# Motor_Control_-_Phase_B.net
KiCad netlist of a schematic drawn in Altium Designer
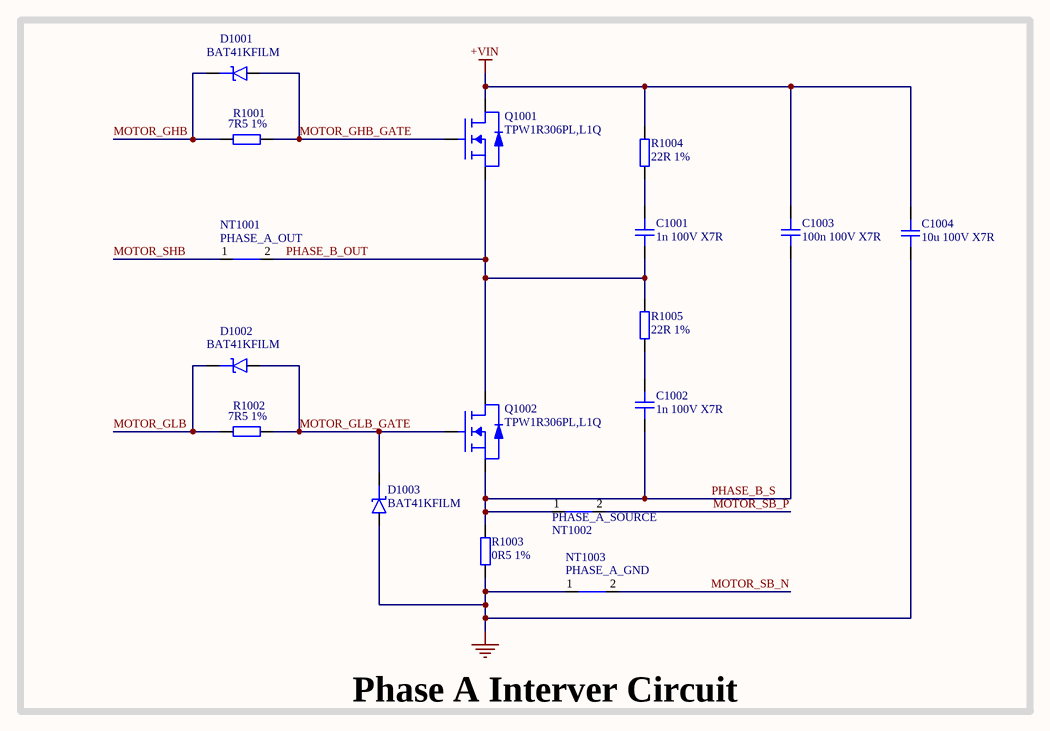
[diagram p0: Motor Control - Phase B.SchDoc]

(export (version "E")
  (design (tool "Eeschema 10.0.6"))
  (components
    (comp (ref "C1001")
      (value "1n 100V X7R")
      (footprint "CAP_0805")
      (description "Capacitor SMD 0805")
      (fields
        (field (name "MANUFACTURER") "Kyocera AVX")
        (field (name "MANUFACTURER PART NUMBER") "08051C102JAT2A")
      )
      (libsource (lib "Schematic-Lib-PhilsLab") (part "CAP_0805"))
    )
    (comp (ref "C1002")
      (value "1n 100V X7R")
      (footprint "CAP_0805")
      (description "Capacitor SMD 0805")
      (fields
        (field (name "MANUFACTURER") "Kyocera AVX")
        (field (name "MANUFACTURER PART NUMBER") "08051C102JAT2A")
      )
      (libsource (lib "Schematic-Lib-PhilsLab") (part "CAP_0805"))
    )
    (comp (ref "C1003")
      (value "100n 100V X7R")
      (footprint "CAP_1206")
      (description "Capacitor SMD 1206")
      (fields
        (field (name "MANUFACTURER") "YAGEO")
        (field (name "MANUFACTURER PART NUMBER") "CC1206JKX7R0BB104")
      )
      (libsource (lib "Schematic-Lib-PhilsLab") (part "CAP_1206"))
    )
    (comp (ref "C1004")
      (value "10u 100V X7R")
      (footprint "CAP_1210")
      (description "Capacitor SMD 1210")
      (fields
        (field (name "MANUFACTURER") "PSA(Prosperity Dielectrics)")
        (field (name "MANUFACTURER PART NUMBER") "FS32X106K101EGG")
      )
      (libsource (lib "Schematic-Lib-PhilsLab") (part "CAP_1210"))
    )
    (comp (ref "D1001")
      (value "BAT41KFILM")
      (footprint "SOD-523")
      (description "Diode Schottky SMD SOD-323")
      (fields (field (name "MANUFACTURER") "STMicroelectronics"))
      (libsource (lib "Schematic-Lib-PhilsLab") (part "D_SCHOTTKY_SOD_523"))
    )
    (comp (ref "D1002")
      (value "BAT41KFILM")
      (footprint "SOD-523")
      (description "Diode Schottky SMD SOD-323")
      (fields (field (name "MANUFACTURER") "STMicroelectronics"))
      (libsource (lib "Schematic-Lib-PhilsLab") (part "D_SCHOTTKY_SOD_523"))
    )
    (comp (ref "D1003")
      (value "BAT41KFILM")
      (footprint "SOD-523")
      (description "Diode Schottky SMD SOD-323")
      (fields (field (name "MANUFACTURER") "STMicroelectronics"))
      (libsource (lib "Schematic-Lib-PhilsLab") (part "D_SCHOTTKY_SOD_523"))
    )
    (comp (ref "NT1001")
      (value "PHASE_A_OUT")
      (footprint "NETTIE_SMD")
      (description "Net Tie SMD")
      (libsource (lib "Schematic-Lib-PhilsLab") (part "NetTie_SMD"))
    )
    (comp (ref "NT1002")
      (value "PHASE_A_SOURCE")
      (footprint "NETTIE_SMD")
      (description "Net Tie SMD")
      (libsource (lib "Schematic-Lib-PhilsLab") (part "NetTie_SMD"))
    )
    (comp (ref "NT1003")
      (value "PHASE_A_GND")
      (footprint "NETTIE_SMD")
      (description "Net Tie SMD")
      (libsource (lib "Schematic-Lib-PhilsLab") (part "NetTie_SMD"))
    )
    (comp (ref "Q1001")
      (value "TPW1R306PL,L1Q")
      (footprint "PowerPAK-SO-8")
      (description "MOSFET N-Channel Vds=30V Id=351A Rds=470uR")
      (fields
        (field (name "MANUFACTURER") "Vishay")
        (field (name "MANUFACTURER PART NUMBER") "SIR500DP-T1-RE3")
      )
      (libsource (lib "Schematic-Lib-PhilsLab") (part "SIR500DP-T1-RE3"))
    )
    (comp (ref "Q1002")
      (value "TPW1R306PL,L1Q")
      (footprint "PowerPAK-SO-8")
      (description "MOSFET N-Channel Vds=30V Id=351A Rds=470uR")
      (fields
        (field (name "MANUFACTURER") "Vishay")
        (field (name "MANUFACTURER PART NUMBER") "SIR500DP-T1-RE3")
      )
      (libsource (lib "Schematic-Lib-PhilsLab") (part "SIR500DP-T1-RE3"))
    )
    (comp (ref "R1001")
      (value "7R5 1%")
      (footprint "RES_0603")
      (description "Resistor SMD 0603")
      (fields
        (field (name "MANUFACTURER") "PANASONIC")
        (field (name "MANUFACTURER PART NUMBER") "ERJPA3J7R5V")
      )
      (libsource (lib "Schematic-Lib-PhilsLab") (part "RES_0603"))
    )
    (comp (ref "R1002")
      (value "7R5 1%")
      (footprint "RES_0603")
      (description "Resistor SMD 0603")
      (fields
        (field (name "MANUFACTURER") "PANASONIC")
        (field (name "MANUFACTURER PART NUMBER") "ERJPA3J7R5V")
      )
      (libsource (lib "Schematic-Lib-PhilsLab") (part "RES_0603"))
    )
    (comp (ref "R1003")
      (value "0R5 1%")
      (footprint "RES_1206")
      (description "Resistor SMD 1206")
      (fields
        (field (name "MANUFACTURER") "Milliohm")
        (field (name "MANUFACTURER PART NUMBER") "HoSRX1206-3W-0.5mR-1%")
      )
      (libsource (lib "Schematic-Lib-PhilsLab") (part "RES_1206"))
    )
    (comp (ref "R1004")
      (value "22R 1%")
      (footprint "RES_0805")
      (description "Resistor SMD 0805")
      (fields
        (field (name "MANUFACTURER") "Viking Tech")
        (field (name "MANUFACTURER PART NUMBER") "ARG05FTC0220")
      )
      (libsource (lib "Schematic-Lib-PhilsLab") (part "RES_0805"))
    )
    (comp (ref "R1005")
      (value "22R 1%")
      (footprint "RES_0805")
      (description "Resistor SMD 0805")
      (fields
        (field (name "MANUFACTURER") "Viking Tech")
        (field (name "MANUFACTURER PART NUMBER") "ARG05FTC0220")
      )
      (libsource (lib "Schematic-Lib-PhilsLab") (part "RES_0805"))
    )
  )
  (nets
    (net (code "1") (name "+VIN") (class "Default")
      (node (ref "C1003") (pin "2") (pinfunction "2_2") (pintype "passive"))
      (node (ref "C1004") (pin "2") (pinfunction "2_2") (pintype "passive"))
      (node (ref "Q1001") (pin "D") (pinfunction "D_D") (pintype "passive"))
      (node (ref "R1004") (pin "2") (pinfunction "2_2") (pintype "passive"))
    )
    (net (code "2") (name "/MOTOR_GHB") (class "Default")
      (node (ref "D1001") (pin "K") (pinfunction "K_K") (pintype "passive"))
      (node (ref "R1001") (pin "1") (pinfunction "1_1") (pintype "passive"))
    )
    (net (code "3") (name "/MOTOR_GHB_GATE") (class "Default")
      (node (ref "D1001") (pin "A") (pinfunction "A_A") (pintype "passive"))
      (node (ref "Q1001") (pin "G") (pinfunction "G_G") (pintype "passive"))
      (node (ref "R1001") (pin "2") (pinfunction "2_2") (pintype "passive"))
    )
    (net (code "4") (name "/MOTOR_GLB") (class "Default")
      (node (ref "D1002") (pin "K") (pinfunction "K_K") (pintype "passive"))
      (node (ref "R1002") (pin "1") (pinfunction "1_1") (pintype "passive"))
    )
    (net (code "5") (name "/MOTOR_GLB_GATE") (class "Default")
      (node (ref "D1002") (pin "A") (pinfunction "A_A") (pintype "passive"))
      (node (ref "D1003") (pin "K") (pinfunction "K_K") (pintype "passive"))
      (node (ref "Q1002") (pin "G") (pinfunction "G_G") (pintype "passive"))
      (node (ref "R1002") (pin "2") (pinfunction "2_2") (pintype "passive"))
    )
    (net (code "6") (name "/MOTOR_SB_N") (class "Default")
      (node (ref "NT1003") (pin "2") (pinfunction "2_2") (pintype "passive"))
    )
    (net (code "7") (name "/MOTOR_SB_P") (class "Default")
      (node (ref "NT1002") (pin "2") (pinfunction "2_2") (pintype "passive"))
    )
    (net (code "8") (name "/MOTOR_SHB") (class "Default")
      (node (ref "NT1001") (pin "1") (pinfunction "1_1") (pintype "passive"))
    )
    (net (code "9") (name "/PHASE_B_OUT") (class "Default")
      (node (ref "C1001") (pin "1") (pinfunction "1_1") (pintype "passive"))
      (node (ref "NT1001") (pin "2") (pinfunction "2_2") (pintype "passive"))
      (node (ref "Q1001") (pin "S") (pinfunction "S_S") (pintype "passive"))
      (node (ref "Q1002") (pin "D") (pinfunction "D_D") (pintype "passive"))
      (node (ref "R1005") (pin "2") (pinfunction "2_2") (pintype "passive"))
    )
    (net (code "10") (name "/PHASE_B_S") (class "Default")
      (node (ref "C1002") (pin "1") (pinfunction "1_1") (pintype "passive"))
      (node (ref "C1003") (pin "1") (pinfunction "1_1") (pintype "passive"))
      (node (ref "NT1002") (pin "1") (pinfunction "1_1") (pintype "passive"))
      (node (ref "Q1002") (pin "S") (pinfunction "S_S") (pintype "passive"))
      (node (ref "R1003") (pin "2") (pinfunction "2_2") (pintype "passive"))
    )
    (net (code "11") (name "GND") (class "Default")
      (node (ref "C1004") (pin "1") (pinfunction "1_1") (pintype "passive"))
      (node (ref "D1003") (pin "A") (pinfunction "A_A") (pintype "passive"))
      (node (ref "NT1003") (pin "1") (pinfunction "1_1") (pintype "passive"))
      (node (ref "R1003") (pin "1") (pinfunction "1_1") (pintype "passive"))
    )
    (net (code "12") (name "Net-(C1001-Pad2)") (class "Default")
      (node (ref "C1001") (pin "2") (pinfunction "2_2") (pintype "passive"))
      (node (ref "R1004") (pin "1") (pinfunction "1_1") (pintype "passive"))
    )
    (net (code "13") (name "Net-(C1002-Pad2)") (class "Default")
      (node (ref "C1002") (pin "2") (pinfunction "2_2") (pintype "passive"))
      (node (ref "R1005") (pin "1") (pinfunction "1_1") (pintype "passive"))
    )
  )
)
